# HallEffect.net
KiCad netlist of a schematic drawn in Altium Designer
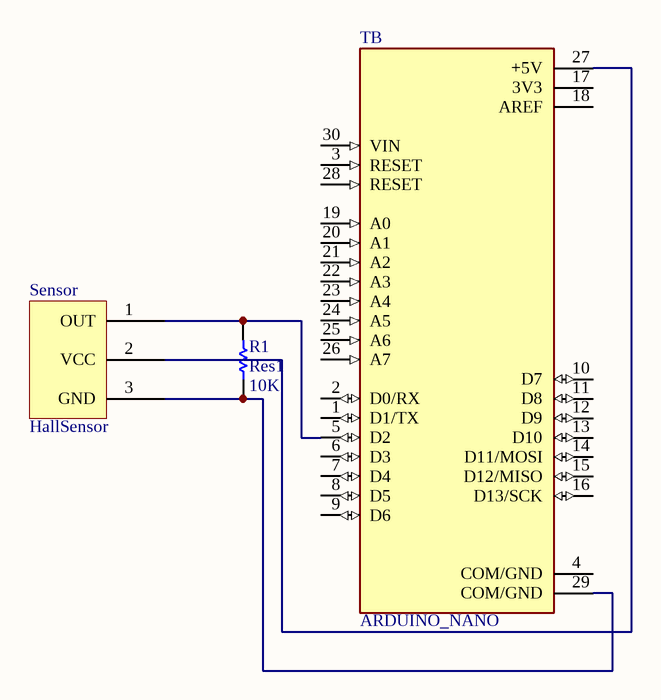
[diagram p0: HallEffect.SchDoc]

(export (version "E")
  (design (tool "Eeschema 10.0.6"))
  (components
    (comp (ref "R1")
      (value "Res1")
      (footprint "AXIAL-0.3")
      (description "Resistor")
      (fields (field (name "ALTIUM_VALUE") "10K") (field (name "PUBLISHER") "Altium Limited"))
      (libsource (lib "Miscellaneous Devices") (part "Res1"))
    )
    (comp (ref "Sensor")
      (value "HallSensor")
      (footprint "HallSensor")
      (libsource (lib "HallEffect") (part "HallSensor"))
    )
    (comp (ref "TB")
      (value "ARDUINO_NANO")
      (footprint "SHIELD_ARDUINO_NANO")
      (description "ATSAMD21G18A Arduino Nano 33 IoT SAM D ARMÂ® CortexÂ®-M0+ MCU 32-Bit Embedded Evaluation Board")
      (fields (field (name "MP") "ARDUINO NANO") (field (name "MF") "Arduino"))
      (libsource (lib "ARDUINO_NANO") (part "ARDUINO_NANO"))
    )
  )
  (nets
    (net (code "1") (name "Net-(Sensor-GND)") (class "Default")
      (node (ref "R1") (pin "1") (pinfunction "1_1") (pintype "passive"))
      (node (ref "Sensor") (pin "3") (pinfunction "GND_3") (pintype "passive"))
      (node (ref "TB") (pin "29") (pinfunction "COM/GND_29") (pintype "power_in"))
    )
    (net (code "2") (name "Net-(Sensor-OUT)") (class "Default")
      (node (ref "R1") (pin "2") (pinfunction "2_2") (pintype "passive"))
      (node (ref "Sensor") (pin "1") (pinfunction "OUT_1") (pintype "passive"))
      (node (ref "TB") (pin "5") (pinfunction "D2_5") (pintype "bidirectional"))
    )
    (net (code "3") (name "Net-(Sensor-VCC)") (class "Default")
      (node (ref "Sensor") (pin "2") (pinfunction "VCC_2") (pintype "passive"))
      (node (ref "TB") (pin "27") (pinfunction "+5V_27") (pintype "power_in"))
    )
    (net (code "4") (name "unconnected-(TB-3V3-Pad17)") (class "Default")
      (node (ref "TB") (pin "17") (pinfunction "3V3_17") (pintype "power_in"))
    )
    (net (code "5") (name "unconnected-(TB-A0-Pad19)") (class "Default")
      (node (ref "TB") (pin "19") (pinfunction "A0_19") (pintype "input"))
    )
    (net (code "6") (name "unconnected-(TB-A1-Pad20)") (class "Default")
      (node (ref "TB") (pin "20") (pinfunction "A1_20") (pintype "input"))
    )
    (net (code "7") (name "unconnected-(TB-A2-Pad21)") (class "Default")
      (node (ref "TB") (pin "21") (pinfunction "A2_21") (pintype "input"))
    )
    (net (code "8") (name "unconnected-(TB-A3-Pad22)") (class "Default")
      (node (ref "TB") (pin "22") (pinfunction "A3_22") (pintype "input"))
    )
    (net (code "9") (name "unconnected-(TB-A4-Pad23)") (class "Default")
      (node (ref "TB") (pin "23") (pinfunction "A4_23") (pintype "input"))
    )
    (net (code "10") (name "unconnected-(TB-A5-Pad24)") (class "Default")
      (node (ref "TB") (pin "24") (pinfunction "A5_24") (pintype "input"))
    )
    (net (code "11") (name "unconnected-(TB-A6-Pad25)") (class "Default")
      (node (ref "TB") (pin "25") (pinfunction "A6_25") (pintype "input"))
    )
    (net (code "12") (name "unconnected-(TB-A7-Pad26)") (class "Default")
      (node (ref "TB") (pin "26") (pinfunction "A7_26") (pintype "input"))
    )
    (net (code "13") (name "unconnected-(TB-AREF-Pad18)") (class "Default")
      (node (ref "TB") (pin "18") (pinfunction "AREF_18") (pintype "power_in"))
    )
    (net (code "14") (name "unconnected-(TB-COM{slash}GND-Pad4)") (class "Default")
      (node (ref "TB") (pin "4") (pinfunction "COM/GND_4") (pintype "power_in"))
    )
    (net (code "15") (name "unconnected-(TB-D0{slash}RX-Pad2)") (class "Default")
      (node (ref "TB") (pin "2") (pinfunction "D0/RX_2") (pintype "bidirectional"))
    )
    (net (code "16") (name "unconnected-(TB-D1{slash}TX-Pad1)") (class "Default")
      (node (ref "TB") (pin "1") (pinfunction "D1/TX_1") (pintype "bidirectional"))
    )
    (net (code "17") (name "unconnected-(TB-D3-Pad6)") (class "Default")
      (node (ref "TB") (pin "6") (pinfunction "D3_6") (pintype "bidirectional"))
    )
    (net (code "18") (name "unconnected-(TB-D4-Pad7)") (class "Default")
      (node (ref "TB") (pin "7") (pinfunction "D4_7") (pintype "bidirectional"))
    )
    (net (code "19") (name "unconnected-(TB-D5-Pad8)") (class "Default")
      (node (ref "TB") (pin "8") (pinfunction "D5_8") (pintype "bidirectional"))
    )
    (net (code "20") (name "unconnected-(TB-D6-Pad9)") (class "Default")
      (node (ref "TB") (pin "9") (pinfunction "D6_9") (pintype "bidirectional"))
    )
    (net (code "21") (name "unconnected-(TB-D7-Pad10)") (class "Default")
      (node (ref "TB") (pin "10") (pinfunction "D7_10") (pintype "bidirectional"))
    )
    (net (code "22") (name "unconnected-(TB-D8-Pad11)") (class "Default")
      (node (ref "TB") (pin "11") (pinfunction "D8_11") (pintype "bidirectional"))
    )
    (net (code "23") (name "unconnected-(TB-D9-Pad12)") (class "Default")
      (node (ref "TB") (pin "12") (pinfunction "D9_12") (pintype "bidirectional"))
    )
    (net (code "24") (name "unconnected-(TB-D10-Pad13)") (class "Default")
      (node (ref "TB") (pin "13") (pinfunction "D10_13") (pintype "bidirectional"))
    )
    (net (code "25") (name "unconnected-(TB-D11{slash}MOSI-Pad14)") (class "Default")
      (node (ref "TB") (pin "14") (pinfunction "D11/MOSI_14") (pintype "bidirectional"))
    )
    (net (code "26") (name "unconnected-(TB-D12{slash}MISO-Pad15)") (class "Default")
      (node (ref "TB") (pin "15") (pinfunction "D12/MISO_15") (pintype "bidirectional"))
    )
    (net (code "27") (name "unconnected-(TB-D13{slash}SCK-Pad16)") (class "Default")
      (node (ref "TB") (pin "16") (pinfunction "D13/SCK_16") (pintype "bidirectional"))
    )
    (net (code "28") (name "unconnected-(TB-RESET-Pad3)") (class "Default")
      (node (ref "TB") (pin "3") (pinfunction "RESET_3") (pintype "input"))
    )
    (net (code "29") (name "unconnected-(TB-RESET-Pad28)") (class "Default")
      (node (ref "TB") (pin "28") (pinfunction "RESET_28") (pintype "input"))
    )
    (net (code "30") (name "unconnected-(TB-VIN-Pad30)") (class "Default")
      (node (ref "TB") (pin "30") (pinfunction "VIN_30") (pintype "input"))
    )
  )
)
